# NSKPD.net
KiCad netlist of a schematic drawn in Altium Designer
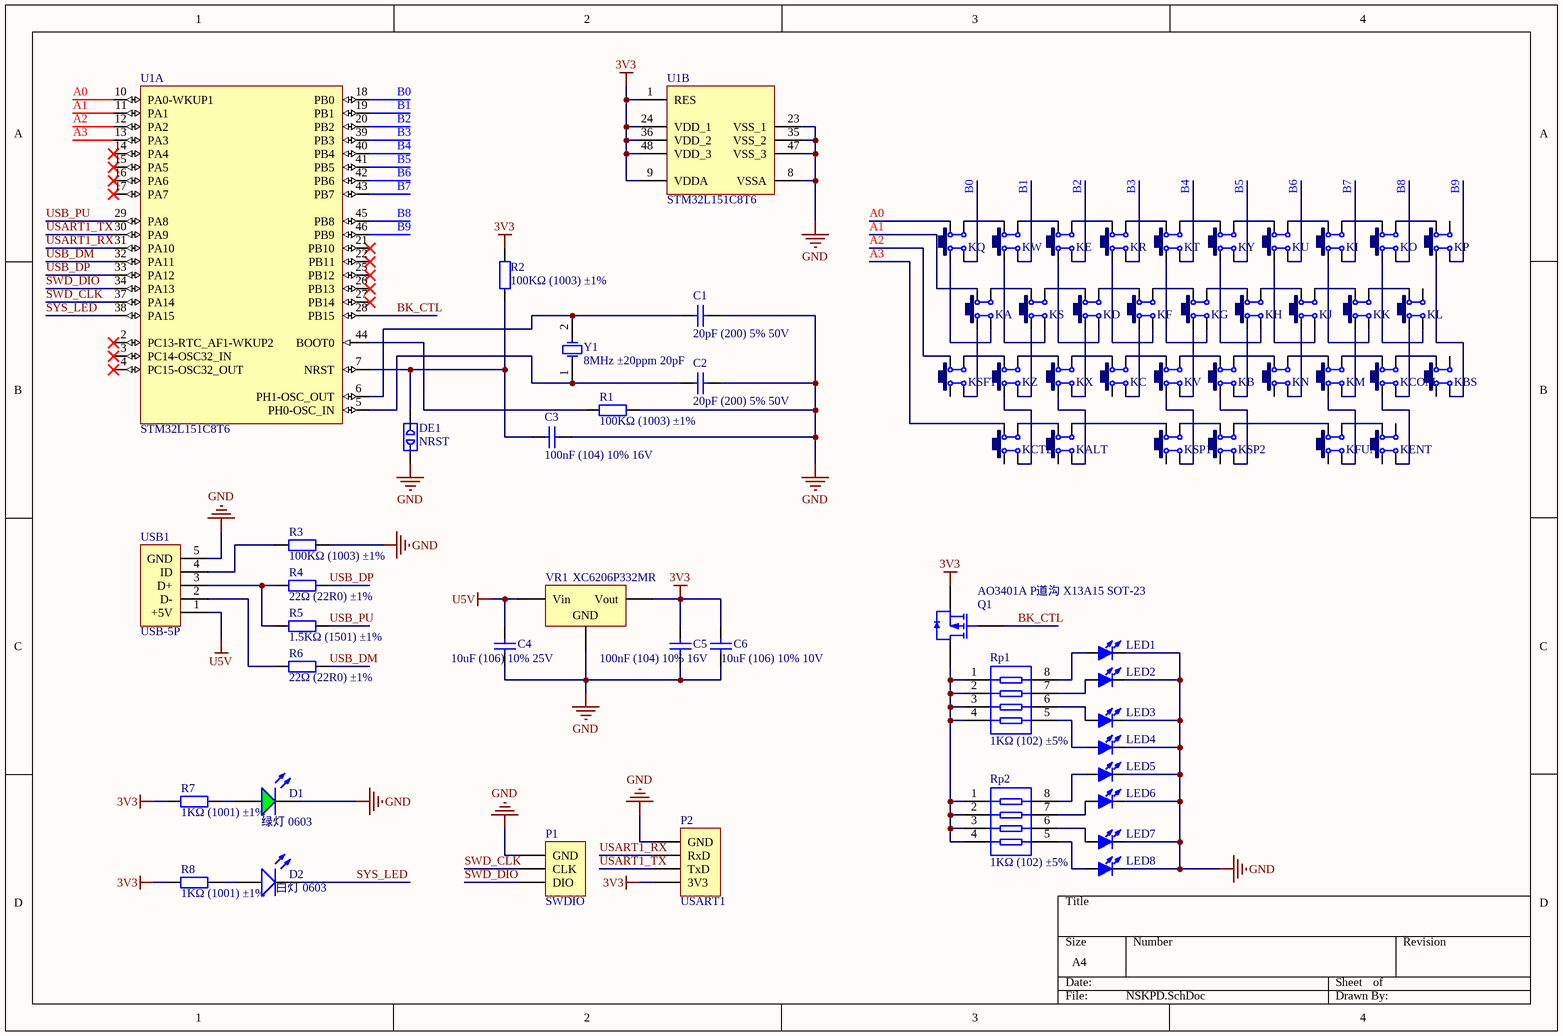
[diagram p0: NSKPD.SchDoc]

(export (version "E")
  (design (tool "Eeschema 10.0.6"))
  (components
    (comp (ref "C1")
      (value "20pF (200) 5% 50V")
      (footprint "0402_C")
      (description "贴片电容")
      (libsource (lib "Miscellaneous Devices LC") (part "0402 20pF (200) 5% 50V"))
    )
    (comp (ref "C2")
      (value "20pF (200) 5% 50V")
      (footprint "0402_C")
      (description "贴片电容")
      (libsource (lib "Miscellaneous Devices LC") (part "0402 20pF (200) 5% 50V"))
    )
    (comp (ref "C3")
      (value "100nF (104) 10% 16V")
      (footprint "0402_C")
      (description "贴片电容")
      (libsource (lib "Miscellaneous Devices LC") (part "0402 100nF (104) 10% 16V"))
    )
    (comp (ref "C4")
      (value "10uF (106) 10% 25V")
      (footprint "0805_C")
      (description "贴片电容")
      (libsource (lib "Miscellaneous Devices LC") (part "0805 10uF (106) 10% 25V"))
    )
    (comp (ref "C5")
      (value "100nF (104) 10% 16V")
      (footprint "0402_C")
      (description "贴片电容")
      (libsource (lib "Miscellaneous Devices LC") (part "0402 100nF (104) 10% 16V"))
    )
    (comp (ref "C6")
      (value "10uF (106) 10% 10V")
      (footprint "0603_C")
      (description "贴片电容")
      (libsource (lib "Miscellaneous Devices LC") (part "0603 10uF (106) 10% 10V"))
    )
    (comp (ref "D1")
      (value "绿灯 0603")
      (footprint "0603_LED_S1")
      (description "发光二极管")
      (libsource (lib "Miscellaneous Devices LC") (part "0603 绿灯"))
    )
    (comp (ref "D2")
      (value "白灯 0603")
      (footprint "0603_LED_S1")
      (description "发光二极管")
      (libsource (lib "Miscellaneous Devices LC") (part "0603 白灯"))
    )
    (comp (ref "DE1")
      (value "NRST")
      (footprint "DEBUG_A")
      (description "调试断点焊盘")
      (fields (field (name "版权归属") "源创客"))
      (libsource (lib "15.1 - 未分类器件") (part "DEBUG"))
    )
    (comp (ref "KA")
      (value "6x6x5")
      (footprint "6*6*4.3 Small")
      (description "贴片6x6轻触开关")
      (fields (field (name "版权归属") "源创客"))
      (libsource (lib "5.1   - 按键-开关") (part "TSW SMD-6x6"))
    )
    (comp (ref "KALT")
      (value "6x6x5")
      (footprint "6*6*4.3 Small")
      (description "贴片6x6轻触开关")
      (fields (field (name "版权归属") "源创客"))
      (libsource (lib "5.1   - 按键-开关") (part "TSW SMD-6x6"))
    )
    (comp (ref "KB")
      (value "6x6x5")
      (footprint "6*6*4.3 Small")
      (description "贴片6x6轻触开关")
      (fields (field (name "版权归属") "源创客"))
      (libsource (lib "5.1   - 按键-开关") (part "TSW SMD-6x6"))
    )
    (comp (ref "KBS")
      (value "6x6x5")
      (footprint "6*6*4.3 Small")
      (description "贴片6x6轻触开关")
      (fields (field (name "版权归属") "源创客"))
      (libsource (lib "5.1   - 按键-开关") (part "TSW SMD-6x6"))
    )
    (comp (ref "KC")
      (value "6x6x5")
      (footprint "6*6*4.3 Small")
      (description "贴片6x6轻触开关")
      (fields (field (name "版权归属") "源创客"))
      (libsource (lib "5.1   - 按键-开关") (part "TSW SMD-6x6"))
    )
    (comp (ref "KCOM")
      (value "6x6x5")
      (footprint "6*6*4.3 Small")
      (description "贴片6x6轻触开关")
      (fields (field (name "版权归属") "源创客"))
      (libsource (lib "5.1   - 按键-开关") (part "TSW SMD-6x6"))
    )
    (comp (ref "KCTL")
      (value "6x6x5")
      (footprint "6*6*4.3 Small")
      (description "贴片6x6轻触开关")
      (fields (field (name "版权归属") "源创客"))
      (libsource (lib "5.1   - 按键-开关") (part "TSW SMD-6x6"))
    )
    (comp (ref "KD")
      (value "6x6x5")
      (footprint "6*6*4.3 Small")
      (description "贴片6x6轻触开关")
      (fields (field (name "版权归属") "源创客"))
      (libsource (lib "5.1   - 按键-开关") (part "TSW SMD-6x6"))
    )
    (comp (ref "KE")
      (value "6x6x5")
      (footprint "6*6*4.3 Small")
      (description "贴片6x6轻触开关")
      (fields (field (name "版权归属") "源创客"))
      (libsource (lib "5.1   - 按键-开关") (part "TSW SMD-6x6"))
    )
    (comp (ref "KENT")
      (value "6x6x5")
      (footprint "6*6*4.3 Small")
      (description "贴片6x6轻触开关")
      (fields (field (name "版权归属") "源创客"))
      (libsource (lib "5.1   - 按键-开关") (part "TSW SMD-6x6"))
    )
    (comp (ref "KF")
      (value "6x6x5")
      (footprint "6*6*4.3 Small")
      (description "贴片6x6轻触开关")
      (fields (field (name "版权归属") "源创客"))
      (libsource (lib "5.1   - 按键-开关") (part "TSW SMD-6x6"))
    )
    (comp (ref "KFUN")
      (value "6x6x5")
      (footprint "6*6*4.3 Small")
      (description "贴片6x6轻触开关")
      (fields (field (name "版权归属") "源创客"))
      (libsource (lib "5.1   - 按键-开关") (part "TSW SMD-6x6"))
    )
    (comp (ref "KG")
      (value "6x6x5")
      (footprint "6*6*4.3 Small")
      (description "贴片6x6轻触开关")
      (fields (field (name "版权归属") "源创客"))
      (libsource (lib "5.1   - 按键-开关") (part "TSW SMD-6x6"))
    )
    (comp (ref "KH")
      (value "6x6x5")
      (footprint "6*6*4.3 Small")
      (description "贴片6x6轻触开关")
      (fields (field (name "版权归属") "源创客"))
      (libsource (lib "5.1   - 按键-开关") (part "TSW SMD-6x6"))
    )
    (comp (ref "KI")
      (value "6x6x5")
      (footprint "6*6*4.3 Small")
      (description "贴片6x6轻触开关")
      (fields (field (name "版权归属") "源创客"))
      (libsource (lib "5.1   - 按键-开关") (part "TSW SMD-6x6"))
    )
    (comp (ref "KJ")
      (value "6x6x5")
      (footprint "6*6*4.3 Small")
      (description "贴片6x6轻触开关")
      (fields (field (name "版权归属") "源创客"))
      (libsource (lib "5.1   - 按键-开关") (part "TSW SMD-6x6"))
    )
    (comp (ref "KK")
      (value "6x6x5")
      (footprint "6*6*4.3 Small")
      (description "贴片6x6轻触开关")
      (fields (field (name "版权归属") "源创客"))
      (libsource (lib "5.1   - 按键-开关") (part "TSW SMD-6x6"))
    )
    (comp (ref "KL")
      (value "6x6x5")
      (footprint "6*6*4.3 Small")
      (description "贴片6x6轻触开关")
      (fields (field (name "版权归属") "源创客"))
      (libsource (lib "5.1   - 按键-开关") (part "TSW SMD-6x6"))
    )
    (comp (ref "KM")
      (value "6x6x5")
      (footprint "6*6*4.3 Small")
      (description "贴片6x6轻触开关")
      (fields (field (name "版权归属") "源创客"))
      (libsource (lib "5.1   - 按键-开关") (part "TSW SMD-6x6"))
    )
    (comp (ref "KN")
      (value "6x6x5")
      (footprint "6*6*4.3 Small")
      (description "贴片6x6轻触开关")
      (fields (field (name "版权归属") "源创客"))
      (libsource (lib "5.1   - 按键-开关") (part "TSW SMD-6x6"))
    )
    (comp (ref "KO")
      (value "6x6x5")
      (footprint "6*6*4.3 Small")
      (description "贴片6x6轻触开关")
      (fields (field (name "版权归属") "源创客"))
      (libsource (lib "5.1   - 按键-开关") (part "TSW SMD-6x6"))
    )
    (comp (ref "KP")
      (value "6x6x5")
      (footprint "6*6*4.3 Small")
      (description "贴片6x6轻触开关")
      (fields (field (name "版权归属") "源创客"))
      (libsource (lib "5.1   - 按键-开关") (part "TSW SMD-6x6"))
    )
    (comp (ref "KQ")
      (value "6x6x5")
      (footprint "6*6*4.3 Small")
      (description "贴片6x6轻触开关")
      (fields (field (name "版权归属") "源创客"))
      (libsource (lib "5.1   - 按键-开关") (part "TSW SMD-6x6"))
    )
    (comp (ref "KR")
      (value "6x6x5")
      (footprint "6*6*4.3 Small")
      (description "贴片6x6轻触开关")
      (fields (field (name "版权归属") "源创客"))
      (libsource (lib "5.1   - 按键-开关") (part "TSW SMD-6x6"))
    )
    (comp (ref "KS")
      (value "6x6x5")
      (footprint "6*6*4.3 Small")
      (description "贴片6x6轻触开关")
      (fields (field (name "版权归属") "源创客"))
      (libsource (lib "5.1   - 按键-开关") (part "TSW SMD-6x6"))
    )
    (comp (ref "KSFT")
      (value "6x6x5")
      (footprint "6*6*4.3 Small")
      (description "贴片6x6轻触开关")
      (fields (field (name "版权归属") "源创客"))
      (libsource (lib "5.1   - 按键-开关") (part "TSW SMD-6x6"))
    )
    (comp (ref "KSP1")
      (value "6x6x5")
      (footprint "6*6*4.3 Small")
      (description "贴片6x6轻触开关")
      (fields (field (name "版权归属") "源创客"))
      (libsource (lib "5.1   - 按键-开关") (part "TSW SMD-6x6"))
    )
    (comp (ref "KSP2")
      (value "6x6x5")
      (footprint "6*6*4.3 Small")
      (description "贴片6x6轻触开关")
      (fields (field (name "版权归属") "源创客"))
      (libsource (lib "5.1   - 按键-开关") (part "TSW SMD-6x6"))
    )
    (comp (ref "KT")
      (value "6x6x5")
      (footprint "6*6*4.3 Small")
      (description "贴片6x6轻触开关")
      (fields (field (name "版权归属") "源创客"))
      (libsource (lib "5.1   - 按键-开关") (part "TSW SMD-6x6"))
    )
    (comp (ref "KU")
      (value "6x6x5")
      (footprint "6*6*4.3 Small")
      (description "贴片6x6轻触开关")
      (fields (field (name "版权归属") "源创客"))
      (libsource (lib "5.1   - 按键-开关") (part "TSW SMD-6x6"))
    )
    (comp (ref "KV")
      (value "6x6x5")
      (footprint "6*6*4.3 Small")
      (description "贴片6x6轻触开关")
      (fields (field (name "版权归属") "源创客"))
      (libsource (lib "5.1   - 按键-开关") (part "TSW SMD-6x6"))
    )
    (comp (ref "KW")
      (value "6x6x5")
      (footprint "6*6*4.3 Small")
      (description "贴片6x6轻触开关")
      (fields (field (name "版权归属") "源创客"))
      (libsource (lib "5.1   - 按键-开关") (part "TSW SMD-6x6"))
    )
    (comp (ref "KX")
      (value "6x6x5")
      (footprint "6*6*4.3 Small")
      (description "贴片6x6轻触开关")
      (fields (field (name "版权归属") "源创客"))
      (libsource (lib "5.1   - 按键-开关") (part "TSW SMD-6x6"))
    )
    (comp (ref "KY")
      (value "6x6x5")
      (footprint "6*6*4.3 Small")
      (description "贴片6x6轻触开关")
      (fields (field (name "版权归属") "源创客"))
      (libsource (lib "5.1   - 按键-开关") (part "TSW SMD-6x6"))
    )
    (comp (ref "KZ")
      (value "6x6x5")
      (footprint "6*6*4.3 Small")
      (description "贴片6x6轻触开关")
      (fields (field (name "版权归属") "源创客"))
      (libsource (lib "5.1   - 按键-开关") (part "TSW SMD-6x6"))
    )
    (comp (ref "LED1")
      (value "侧发光")
      (footprint "LED 0805W")
      (description "贴片LED")
      (fields (field (name "版权归属") "源创客"))
      (libsource (lib "9.1   - LED") (part "LED-SMD"))
    )
    (comp (ref "LED2")
      (value "侧发光")
      (footprint "LED 0805W")
      (description "贴片LED")
      (fields (field (name "版权归属") "源创客"))
      (libsource (lib "9.1   - LED") (part "LED-SMD"))
    )
    (comp (ref "LED3")
      (value "侧发光")
      (footprint "LED 0805W")
      (description "贴片LED")
      (fields (field (name "版权归属") "源创客"))
      (libsource (lib "9.1   - LED") (part "LED-SMD"))
    )
    (comp (ref "LED4")
      (value "侧发光")
      (footprint "LED 0805W")
      (description "贴片LED")
      (fields (field (name "版权归属") "源创客"))
      (libsource (lib "9.1   - LED") (part "LED-SMD"))
    )
    (comp (ref "LED5")
      (value "侧发光")
      (footprint "LED 0805W")
      (description "贴片LED")
      (fields (field (name "版权归属") "源创客"))
      (libsource (lib "9.1   - LED") (part "LED-SMD"))
    )
    (comp (ref "LED6")
      (value "侧发光")
      (footprint "LED 0805W")
      (description "贴片LED")
      (fields (field (name "版权归属") "源创客"))
      (libsource (lib "9.1   - LED") (part "LED-SMD"))
    )
    (comp (ref "LED7")
      (value "侧发光")
      (footprint "LED 0805W")
      (description "贴片LED")
      (fields (field (name "版权归属") "源创客"))
      (libsource (lib "9.1   - LED") (part "LED-SMD"))
    )
    (comp (ref "LED8")
      (value "侧发光")
      (footprint "LED 0805W")
      (description "贴片LED")
      (fields (field (name "版权归属") "源创客"))
      (libsource (lib "9.1   - LED") (part "LED-SMD"))
    )
    (comp (ref "P1")
      (value "SWDIO")
      (footprint "HDR1X3")
      (description "Header, 3-Pin")
      (fields (field (name "PUBLISHER") "Altium Limited"))
      (libsource (lib "Miscellaneous Connectors") (part "Header 3"))
    )
    (comp (ref "P2")
      (value "USART1")
      (footprint "HDR1X4")
      (description "Header, 4-Pin")
      (fields (field (name "PUBLISHER") "Altium Limited"))
      (libsource (lib "Miscellaneous Connectors") (part "Header 4"))
    )
    (comp (ref "Q1")
      (value "AO3401A P道沟 X13A15 SOT-23")
      (footprint "SOT-23-3L")
      (description "MOS(场效应管)")
      (libsource (lib "Miscellaneous Devices LC") (part "AO3401A P道沟 X13A15 SOT-23"))
    )
    (comp (ref "R1")
      (value "100KΩ (1003) ±1%")
      (footprint "0402_R")
      (description "贴片电阻")
      (libsource (lib "Miscellaneous Devices LC") (part "0402 100KΩ (1003) 1%"))
    )
    (comp (ref "R2")
      (value "100KΩ (1003) ±1%")
      (footprint "0402_R")
      (description "贴片电阻")
      (libsource (lib "") (part "0402 100KΩ (1003) 1%_1"))
    )
    (comp (ref "R3")
      (value "100KΩ (1003) ±1%")
      (footprint "0402_R")
      (description "贴片电阻")
      (libsource (lib "Miscellaneous Devices LC") (part "0402 100KΩ (1003) 1%"))
    )
    (comp (ref "R4")
      (value "22Ω (22R0) ±1%")
      (footprint "0402_R")
      (description "贴片电阻")
      (libsource (lib "Miscellaneous Devices LC") (part "0402 22Ω (22R0) 1%"))
    )
    (comp (ref "R5")
      (value "1.5KΩ (1501) ±1%")
      (footprint "0402_R")
      (description "贴片电阻")
      (libsource (lib "Miscellaneous Devices LC") (part "0402 1.5KΩ (1501) 1%"))
    )
    (comp (ref "R6")
      (value "22Ω (22R0) ±1%")
      (footprint "0402_R")
      (description "贴片电阻")
      (libsource (lib "Miscellaneous Devices LC") (part "0402 22Ω (22R0) 1%"))
    )
    (comp (ref "R7")
      (value "1KΩ (1001) ±1%")
      (footprint "0402_R")
      (description "贴片电阻")
      (libsource (lib "") (part "0402 1KΩ (1001) 1%_1"))
    )
    (comp (ref "R8")
      (value "1KΩ (1001) ±1%")
      (footprint "0402_R")
      (description "贴片电阻")
      (libsource (lib "Miscellaneous Devices LC") (part "0402 1KΩ (1001) 1%"))
    )
    (comp (ref "Rp1")
      (value "1KΩ (102) ±5%")
      (footprint "0402_Rx4")
      (description "贴片排阻")
      (libsource (lib "Miscellaneous Devices LC") (part "0402*4 1KΩ (102) 5%"))
    )
    (comp (ref "Rp2")
      (value "1KΩ (102) ±5%")
      (footprint "0402_Rx4")
      (description "贴片排阻")
      (libsource (lib "Miscellaneous Devices LC") (part "0402*4 1KΩ (102) 5%"))
    )
    (comp (ref "U1")
      (value "STM32L151C8T6")
      (footprint "LQFP-48_7x7x05P")
      (description "ARM")
      (libsource (lib "Miscellaneous Devices LC") (part "STM32L151C8T6"))
    )
    (comp (ref "USB1")
      (value "USB-5P")
      (footprint "USB-MICRO_D")
      (description "微型USB母座")
      (fields (field (name "版权归属") "源创客"))
      (libsource (lib "4.1   - 接口类") (part "USB-5P"))
    )
    (comp (ref "VR1")
      (value "XC6206P332MR")
      (footprint "SOT-23-3L")
      (description "低压差线性稳压(LDO)")
      (libsource (lib "Miscellaneous Devices LC") (part "SOT-23 XC6206P332MR"))
    )
    (comp (ref "Y1")
      (value "8MHz ±20ppm 20pF")
      (footprint "SMD-5032_2P")
      (description "贴片晶振")
      (libsource (lib "Miscellaneous Devices LC") (part "SMD-5032_2P 8MHz 20ppm 20pF"))
    )
  )
  (nets
    (net (code "1") (name "/A0") (class "Default")
      (node (ref "KQ") (pin "2") (pinfunction "2_2") (pintype "passive"))
      (node (ref "U1") (pin "10") (pinfunction "PA0-WKUP1_10") (pintype "bidirectional"))
    )
    (net (code "2") (name "/A1") (class "Default")
      (node (ref "KA") (pin "2") (pinfunction "2_2") (pintype "passive"))
      (node (ref "U1") (pin "11") (pinfunction "PA1_11") (pintype "bidirectional"))
    )
    (net (code "3") (name "/A2") (class "Default")
      (node (ref "KSFT") (pin "2") (pinfunction "2_2") (pintype "passive"))
      (node (ref "U1") (pin "12") (pinfunction "PA2_12") (pintype "bidirectional"))
    )
    (net (code "4") (name "/A3") (class "Default")
      (node (ref "KCTL") (pin "2") (pinfunction "2_2") (pintype "passive"))
      (node (ref "U1") (pin "13") (pinfunction "PA3_13") (pintype "bidirectional"))
    )
    (net (code "5") (name "/B0") (class "Default")
      (node (ref "KQ") (pin "4") (pinfunction "4_4") (pintype "passive"))
      (node (ref "U1") (pin "18") (pinfunction "PB0_18") (pintype "bidirectional"))
    )
    (net (code "6") (name "/B1") (class "Default")
      (node (ref "KW") (pin "4") (pinfunction "4_4") (pintype "passive"))
      (node (ref "U1") (pin "19") (pinfunction "PB1_19") (pintype "bidirectional"))
    )
    (net (code "7") (name "/B2") (class "Default")
      (node (ref "KE") (pin "4") (pinfunction "4_4") (pintype "passive"))
      (node (ref "U1") (pin "20") (pinfunction "PB2_20") (pintype "bidirectional"))
    )
    (net (code "8") (name "/B3") (class "Default")
      (node (ref "KR") (pin "4") (pinfunction "4_4") (pintype "passive"))
      (node (ref "U1") (pin "39") (pinfunction "PB3_39") (pintype "bidirectional"))
    )
    (net (code "9") (name "/B4") (class "Default")
      (node (ref "KT") (pin "4") (pinfunction "4_4") (pintype "passive"))
      (node (ref "U1") (pin "40") (pinfunction "PB4_40") (pintype "bidirectional"))
    )
    (net (code "10") (name "/B5") (class "Default")
      (node (ref "KY") (pin "4") (pinfunction "4_4") (pintype "passive"))
      (node (ref "U1") (pin "41") (pinfunction "PB5_41") (pintype "bidirectional"))
    )
    (net (code "11") (name "/B6") (class "Default")
      (node (ref "KU") (pin "4") (pinfunction "4_4") (pintype "passive"))
      (node (ref "U1") (pin "42") (pinfunction "PB6_42") (pintype "bidirectional"))
    )
    (net (code "12") (name "/B7") (class "Default")
      (node (ref "KI") (pin "4") (pinfunction "4_4") (pintype "passive"))
      (node (ref "U1") (pin "43") (pinfunction "PB7_43") (pintype "bidirectional"))
    )
    (net (code "13") (name "/B8") (class "Default")
      (node (ref "KO") (pin "4") (pinfunction "4_4") (pintype "passive"))
      (node (ref "U1") (pin "45") (pinfunction "PB8_45") (pintype "bidirectional"))
    )
    (net (code "14") (name "/B9") (class "Default")
      (node (ref "KP") (pin "4") (pinfunction "4_4") (pintype "passive"))
      (node (ref "U1") (pin "46") (pinfunction "PB9_46") (pintype "bidirectional"))
    )
    (net (code "15") (name "/BK_CTL") (class "Default")
      (node (ref "Q1") (pin "1") (pinfunction "G_1") (pintype "passive"))
      (node (ref "U1") (pin "28") (pinfunction "PB15_28") (pintype "bidirectional"))
    )
    (net (code "16") (name "/SWD_CLK") (class "Default")
      (node (ref "P1") (pin "2") (pinfunction "CLK_2") (pintype "passive"))
      (node (ref "U1") (pin "37") (pinfunction "PA14_37") (pintype "bidirectional"))
    )
    (net (code "17") (name "/SWD_DIO") (class "Default")
      (node (ref "P1") (pin "3") (pinfunction "DIO_3") (pintype "passive"))
      (node (ref "U1") (pin "34") (pinfunction "PA13_34") (pintype "bidirectional"))
    )
    (net (code "18") (name "/SYS_LED") (class "Default")
      (node (ref "D2") (pin "K") (pinfunction "K_K") (pintype "passive"))
      (node (ref "U1") (pin "38") (pinfunction "PA15_38") (pintype "bidirectional"))
    )
    (net (code "19") (name "/USART1_RX") (class "Default")
      (node (ref "P2") (pin "2") (pinfunction "RxD_2") (pintype "passive"))
      (node (ref "U1") (pin "31") (pinfunction "PA10_31") (pintype "bidirectional"))
    )
    (net (code "20") (name "/USART1_TX") (class "Default")
      (node (ref "P2") (pin "3") (pinfunction "TxD_3") (pintype "passive"))
      (node (ref "U1") (pin "30") (pinfunction "PA9_30") (pintype "bidirectional"))
    )
    (net (code "21") (name "/USB_DM") (class "Default")
      (node (ref "R6") (pin "2") (pinfunction "2_2") (pintype "passive"))
      (node (ref "U1") (pin "32") (pinfunction "PA11_32") (pintype "bidirectional"))
    )
    (net (code "22") (name "/USB_DP") (class "Default")
      (node (ref "R4") (pin "2") (pinfunction "2_2") (pintype "passive"))
      (node (ref "U1") (pin "33") (pinfunction "PA12_33") (pintype "bidirectional"))
    )
    (net (code "23") (name "/USB_PU") (class "Default")
      (node (ref "R5") (pin "2") (pinfunction "2_2") (pintype "passive"))
      (node (ref "U1") (pin "29") (pinfunction "PA8_29") (pintype "bidirectional"))
    )
    (net (code "24") (name "3V3") (class "Default")
      (node (ref "C5") (pin "2") (pinfunction "2_2") (pintype "passive"))
      (node (ref "C6") (pin "2") (pinfunction "2_2") (pintype "passive"))
      (node (ref "P2") (pin "4") (pinfunction "3V3_4") (pintype "passive"))
      (node (ref "Q1") (pin "2") (pinfunction "S_2") (pintype "passive"))
      (node (ref "R2") (pin "2") (pinfunction "2_2") (pintype "passive"))
      (node (ref "R7") (pin "1") (pinfunction "1_1") (pintype "passive"))
      (node (ref "R8") (pin "2") (pinfunction "2_2") (pintype "passive"))
      (node (ref "U1") (pin "1") (pinfunction "RES_1") (pintype "power_in"))
      (node (ref "U1") (pin "24") (pinfunction "VDD_1_24") (pintype "power_in"))
      (node (ref "U1") (pin "36") (pinfunction "VDD_2_36") (pintype "power_in"))
      (node (ref "U1") (pin "48") (pinfunction "VDD_3_48") (pintype "power_in"))
      (node (ref "U1") (pin "9") (pinfunction "VDDA_9") (pintype "power_in"))
      (node (ref "VR1") (pin "2") (pinfunction "Vout_2") (pintype "passive"))
    )
    (net (code "25") (name "GND") (class "Default")
      (node (ref "C1") (pin "2") (pinfunction "2_2") (pintype "passive"))
      (node (ref "C2") (pin "2") (pinfunction "2_2") (pintype "passive"))
      (node (ref "C3") (pin "1") (pinfunction "1_1") (pintype "passive"))
      (node (ref "C4") (pin "1") (pinfunction "1_1") (pintype "passive"))
      (node (ref "C5") (pin "1") (pinfunction "1_1") (pintype "passive"))
      (node (ref "C6") (pin "1") (pinfunction "1_1") (pintype "passive"))
      (node (ref "D1") (pin "K") (pinfunction "K_K") (pintype "passive"))
      (node (ref "DE1") (pin "2") (pinfunction "2_2") (pintype "passive"))
      (node (ref "LED1") (pin "2") (pinfunction "K_2") (pintype "passive"))
      (node (ref "LED2") (pin "2") (pinfunction "K_2") (pintype "passive"))
      (node (ref "LED3") (pin "2") (pinfunction "K_2") (pintype "passive"))
      (node (ref "LED4") (pin "2") (pinfunction "K_2") (pintype "passive"))
      (node (ref "LED5") (pin "2") (pinfunction "K_2") (pintype "passive"))
      (node (ref "LED6") (pin "2") (pinfunction "K_2") (pintype "passive"))
      (node (ref "LED7") (pin "2") (pinfunction "K_2") (pintype "passive"))
      (node (ref "LED8") (pin "2") (pinfunction "K_2") (pintype "passive"))
      (node (ref "P1") (pin "1") (pinfunction "GND_1") (pintype "passive"))
      (node (ref "P2") (pin "1") (pinfunction "GND_1") (pintype "passive"))
      (node (ref "R1") (pin "2") (pinfunction "2_2") (pintype "passive"))
      (node (ref "R3") (pin "2") (pinfunction "2_2") (pintype "passive"))
      (node (ref "U1") (pin "23") (pinfunction "VSS_1_23") (pintype "power_in"))
      (node (ref "U1") (pin "35") (pinfunction "VSS_2_35") (pintype "power_in"))
      (node (ref "U1") (pin "47") (pinfunction "VSS_3_47") (pintype "power_in"))
      (node (ref "U1") (pin "8") (pinfunction "VSSA_8") (pintype "power_in"))
      (node (ref "USB1") (pin "5") (pinfunction "GND_5") (pintype "passive"))
      (node (ref "VR1") (pin "1") (pinfunction "GND_1") (pintype "passive"))
    )
    (net (code "26") (name "Net-(D1-PadA)") (class "Default")
      (node (ref "D1") (pin "A") (pinfunction "A_A") (pintype "passive"))
      (node (ref "R7") (pin "2") (pinfunction "2_2") (pintype "passive"))
    )
    (net (code "27") (name "Net-(D2-PadA)") (class "Default")
      (node (ref "D2") (pin "A") (pinfunction "A_A") (pintype "passive"))
      (node (ref "R8") (pin "1") (pinfunction "1_1") (pintype "passive"))
    )
    (net (code "28") (name "Net-(KA-Pad1)") (class "Default")
      (node (ref "KA") (pin "1") (pinfunction "1_1") (pintype "passive"))
      (node (ref "KSFT") (pin "4") (pinfunction "4_4") (pintype "passive"))
    )
    (net (code "29") (name "Net-(KA-Pad3)") (class "Default")
      (node (ref "KA") (pin "3") (pinfunction "3_3") (pintype "passive"))
      (node (ref "KS") (pin "2") (pinfunction "2_2") (pintype "passive"))
    )
    (net (code "30") (name "Net-(KA-Pad4)") (class "Default")
      (node (ref "KA") (pin "4") (pinfunction "4_4") (pintype "passive"))
      (node (ref "KQ") (pin "1") (pinfunction "1_1") (pintype "passive"))
    )
    (net (code "31") (name "Net-(KALT-Pad2)") (class "Default")
      (node (ref "KALT") (pin "2") (pinfunction "2_2") (pintype "passive"))
      (node (ref "KCTL") (pin "3") (pinfunction "3_3") (pintype "passive"))
    )
    (net (code "32") (name "Net-(KALT-Pad3)") (class "Default")
      (node (ref "KALT") (pin "3") (pinfunction "3_3") (pintype "passive"))
      (node (ref "KSP1") (pin "2") (pinfunction "2_2") (pintype "passive"))
    )
    (net (code "33") (name "Net-(KALT-Pad4)") (class "Default")
      (node (ref "KALT") (pin "4") (pinfunction "4_4") (pintype "passive"))
      (node (ref "KX") (pin "1") (pinfunction "1_1") (pintype "passive"))
    )
    (net (code "34") (name "Net-(KB-Pad1)") (class "Default")
      (node (ref "KB") (pin "1") (pinfunction "1_1") (pintype "passive"))
      (node (ref "KSP2") (pin "4") (pinfunction "4_4") (pintype "passive"))
    )
    (net (code "35") (name "Net-(KB-Pad2)") (class "Default")
      (node (ref "KB") (pin "2") (pinfunction "2_2") (pintype "passive"))
      (node (ref "KV") (pin "3") (pinfunction "3_3") (pintype "passive"))
    )
    (net (code "36") (name "Net-(KB-Pad3)") (class "Default")
      (node (ref "KB") (pin "3") (pinfunction "3_3") (pintype "passive"))
      (node (ref "KN") (pin "2") (pinfunction "2_2") (pintype "passive"))
    )
    (net (code "37") (name "Net-(KB-Pad4)") (class "Default")
      (node (ref "KB") (pin "4") (pinfunction "4_4") (pintype "passive"))
      (node (ref "KH") (pin "1") (pinfunction "1_1") (pintype "passive"))
    )
    (net (code "38") (name "Net-(KBS-Pad2)") (class "Default")
      (node (ref "KBS") (pin "2") (pinfunction "2_2") (pintype "passive"))
      (node (ref "KCOM") (pin "3") (pinfunction "3_3") (pintype "passive"))
    )
    (net (code "39") (name "Net-(KBS-Pad4)") (class "Default")
      (node (ref "KBS") (pin "4") (pinfunction "4_4") (pintype "passive"))
      (node (ref "KP") (pin "1") (pinfunction "1_1") (pintype "passive"))
    )
    (net (code "40") (name "Net-(KC-Pad2)") (class "Default")
      (node (ref "KC") (pin "2") (pinfunction "2_2") (pintype "passive"))
      (node (ref "KX") (pin "3") (pinfunction "3_3") (pintype "passive"))
    )
    (net (code "41") (name "Net-(KC-Pad3)") (class "Default")
      (node (ref "KC") (pin "3") (pinfunction "3_3") (pintype "passive"))
      (node (ref "KV") (pin "2") (pinfunction "2_2") (pintype "passive"))
    )
    (net (code "42") (name "Net-(KC-Pad4)") (class "Default")
      (node (ref "KC") (pin "4") (pinfunction "4_4") (pintype "passive"))
      (node (ref "KF") (pin "1") (pinfunction "1_1") (pintype "passive"))
    )
    (net (code "43") (name "Net-(KCOM-Pad1)") (class "Default")
      (node (ref "KCOM") (pin "1") (pinfunction "1_1") (pintype "passive"))
      (node (ref "KENT") (pin "4") (pinfunction "4_4") (pintype "passive"))
    )
    (net (code "44") (name "Net-(KCOM-Pad2)") (class "Default")
      (node (ref "KCOM") (pin "2") (pinfunction "2_2") (pintype "passive"))
      (node (ref "KM") (pin "3") (pinfunction "3_3") (pintype "passive"))
    )
    (net (code "45") (name "Net-(KCOM-Pad4)") (class "Default")
      (node (ref "KCOM") (pin "4") (pinfunction "4_4") (pintype "passive"))
      (node (ref "KL") (pin "1") (pinfunction "1_1") (pintype "passive"))
    )
    (net (code "46") (name "Net-(KCTL-Pad4)") (class "Default")
      (node (ref "KCTL") (pin "4") (pinfunction "4_4") (pintype "passive"))
      (node (ref "KZ") (pin "1") (pinfunction "1_1") (pintype "passive"))
    )
    (net (code "47") (name "Net-(KD-Pad1)") (class "Default")
      (node (ref "KD") (pin "1") (pinfunction "1_1") (pintype "passive"))
      (node (ref "KX") (pin "4") (pinfunction "4_4") (pintype "passive"))
    )
    (net (code "48") (name "Net-(KD-Pad2)") (class "Default")
      (node (ref "KD") (pin "2") (pinfunction "2_2") (pintype "passive"))
      (node (ref "KS") (pin "3") (pinfunction "3_3") (pintype "passive"))
    )
    (net (code "49") (name "Net-(KD-Pad3)") (class "Default")
      (node (ref "KD") (pin "3") (pinfunction "3_3") (pintype "passive"))
      (node (ref "KF") (pin "2") (pinfunction "2_2") (pintype "passive"))
    )
    (net (code "50") (name "Net-(KD-Pad4)") (class "Default")
      (node (ref "KD") (pin "4") (pinfunction "4_4") (pintype "passive"))
      (node (ref "KE") (pin "1") (pinfunction "1_1") (pintype "passive"))
    )
    (net (code "51") (name "Net-(KE-Pad2)") (class "Default")
      (node (ref "KE") (pin "2") (pinfunction "2_2") (pintype "passive"))
      (node (ref "KW") (pin "3") (pinfunction "3_3") (pintype "passive"))
    )
    (net (code "52") (name "Net-(KE-Pad3)") (class "Default")
      (node (ref "KE") (pin "3") (pinfunction "3_3") (pintype "passive"))
      (node (ref "KR") (pin "2") (pinfunction "2_2") (pintype "passive"))
    )
    (net (code "53") (name "Net-(KENT-Pad2)") (class "Default")
      (node (ref "KENT") (pin "2") (pinfunction "2_2") (pintype "passive"))
      (node (ref "KFUN") (pin "3") (pinfunction "3_3") (pintype "passive"))
    )
    (net (code "54") (name "Net-(KF-Pad3)") (class "Default")
      (node (ref "KF") (pin "3") (pinfunction "3_3") (pintype "passive"))
      (node (ref "KG") (pin "2") (pinfunction "2_2") (pintype "passive"))
    )
    (net (code "55") (name "Net-(KF-Pad4)") (class "Default")
      (node (ref "KF") (pin "4") (pinfunction "4_4") (pintype "passive"))
      (node (ref "KR") (pin "1") (pinfunction "1_1") (pintype "passive"))
    )
    (net (code "56") (name "Net-(KFUN-Pad2)") (class "Default")
      (node (ref "KFUN") (pin "2") (pinfunction "2_2") (pintype "passive"))
      (node (ref "KSP2") (pin "3") (pinfunction "3_3") (pintype "passive"))
    )
    (net (code "57") (name "Net-(KFUN-Pad4)") (class "Default")
      (node (ref "KFUN") (pin "4") (pinfunction "4_4") (pintype "passive"))
      (node (ref "KM") (pin "1") (pinfunction "1_1") (pintype "passive"))
    )
    (net (code "58") (name "Net-(KG-Pad1)") (class "Default")
      (node (ref "KG") (pin "1") (pinfunction "1_1") (pintype "passive"))
      (node (ref "KV") (pin "4") (pinfunction "4_4") (pintype "passive"))
    )
    (net (code "59") (name "Net-(KG-Pad3)") (class "Default")
      (node (ref "KG") (pin "3") (pinfunction "3_3") (pintype "passive"))
      (node (ref "KH") (pin "2") (pinfunction "2_2") (pintype "passive"))
    )
    (net (code "60") (name "Net-(KG-Pad4)") (class "Default")
      (node (ref "KG") (pin "4") (pinfunction "4_4") (pintype "passive"))
      (node (ref "KT") (pin "1") (pinfunction "1_1") (pintype "passive"))
    )
    (net (code "61") (name "Net-(KH-Pad3)") (class "Default")
      (node (ref "KH") (pin "3") (pinfunction "3_3") (pintype "passive"))
      (node (ref "KJ") (pin "2") (pinfunction "2_2") (pintype "passive"))
    )
    (net (code "62") (name "Net-(KH-Pad4)") (class "Default")
      (node (ref "KH") (pin "4") (pinfunction "4_4") (pintype "passive"))
      (node (ref "KY") (pin "1") (pinfunction "1_1") (pintype "passive"))
    )
    (net (code "63") (name "Net-(KI-Pad1)") (class "Default")
      (node (ref "KI") (pin "1") (pinfunction "1_1") (pintype "passive"))
      (node (ref "KK") (pin "4") (pinfunction "4_4") (pintype "passive"))
    )
    (net (code "64") (name "Net-(KI-Pad2)") (class "Default")
      (node (ref "KI") (pin "2") (pinfunction "2_2") (pintype "passive"))
      (node (ref "KU") (pin "3") (pinfunction "3_3") (pintype "passive"))
    )
    (net (code "65") (name "Net-(KI-Pad3)") (class "Default")
      (node (ref "KI") (pin "3") (pinfunction "3_3") (pintype "passive"))
      (node (ref "KO") (pin "2") (pinfunction "2_2") (pintype "passive"))
    )
    (net (code "66") (name "Net-(KJ-Pad1)") (class "Default")
      (node (ref "KJ") (pin "1") (pinfunction "1_1") (pintype "passive"))
      (node (ref "KN") (pin "4") (pinfunction "4_4") (pintype "passive"))
    )
    (net (code "67") (name "Net-(KJ-Pad3)") (class "Default")
      (node (ref "KJ") (pin "3") (pinfunction "3_3") (pintype "passive"))
      (node (ref "KK") (pin "2") (pinfunction "2_2") (pintype "passive"))
    )
    (net (code "68") (name "Net-(KJ-Pad4)") (class "Default")
      (node (ref "KJ") (pin "4") (pinfunction "4_4") (pintype "passive"))
      (node (ref "KU") (pin "1") (pinfunction "1_1") (pintype "passive"))
    )
    (net (code "69") (name "Net-(KK-Pad1)") (class "Default")
      (node (ref "KK") (pin "1") (pinfunction "1_1") (pintype "passive"))
      (node (ref "KM") (pin "4") (pinfunction "4_4") (pintype "passive"))
    )
    (net (code "70") (name "Net-(KK-Pad3)") (class "Default")
      (node (ref "KK") (pin "3") (pinfunction "3_3") (pintype "passive"))
      (node (ref "KL") (pin "2") (pinfunction "2_2") (pintype "passive"))
    )
    (net (code "71") (name "Net-(KL-Pad4)") (class "Default")
      (node (ref "KL") (pin "4") (pinfunction "4_4") (pintype "passive"))
      (node (ref "KO") (pin "1") (pinfunction "1_1") (pintype "passive"))
    )
    (net (code "72") (name "Net-(KM-Pad2)") (class "Default")
      (node (ref "KM") (pin "2") (pinfunction "2_2") (pintype "passive"))
      (node (ref "KN") (pin "3") (pinfunction "3_3") (pintype "passive"))
    )
    (net (code "73") (name "Net-(KO-Pad3)") (class "Default")
      (node (ref "KO") (pin "3") (pinfunction "3_3") (pintype "passive"))
      (node (ref "KP") (pin "2") (pinfunction "2_2") (pintype "passive"))
    )
    (net (code "74") (name "Net-(KQ-Pad3)") (class "Default")
      (node (ref "KQ") (pin "3") (pinfunction "3_3") (pintype "passive"))
      (node (ref "KW") (pin "2") (pinfunction "2_2") (pintype "passive"))
    )
    (net (code "75") (name "Net-(KR-Pad3)") (class "Default")
      (node (ref "KR") (pin "3") (pinfunction "3_3") (pintype "passive"))
      (node (ref "KT") (pin "2") (pinfunction "2_2") (pintype "passive"))
    )
    (net (code "76") (name "Net-(KS-Pad1)") (class "Default")
      (node (ref "KS") (pin "1") (pinfunction "1_1") (pintype "passive"))
      (node (ref "KZ") (pin "4") (pinfunction "4_4") (pintype "passive"))
    )
    (net (code "77") (name "Net-(KS-Pad4)") (class "Default")
      (node (ref "KS") (pin "4") (pinfunction "4_4") (pintype "passive"))
      (node (ref "KW") (pin "1") (pinfunction "1_1") (pintype "passive"))
    )
    (net (code "78") (name "Net-(KSFT-Pad3)") (class "Default")
      (node (ref "KSFT") (pin "3") (pinfunction "3_3") (pintype "passive"))
      (node (ref "KZ") (pin "2") (pinfunction "2_2") (pintype "passive"))
    )
    (net (code "79") (name "Net-(KSP1-Pad3)") (class "Default")
      (node (ref "KSP1") (pin "3") (pinfunction "3_3") (pintype "passive"))
      (node (ref "KSP2") (pin "2") (pinfunction "2_2") (pintype "passive"))
    )
    (net (code "80") (name "Net-(KSP1-Pad4)") (class "Default")
      (node (ref "KSP1") (pin "4") (pinfunction "4_4") (pintype "passive"))
      (node (ref "KV") (pin "1") (pinfunction "1_1") (pintype "passive"))
    )
    (net (code "81") (name "Net-(KT-Pad3)") (class "Default")
      (node (ref "KT") (pin "3") (pinfunction "3_3") (pintype "passive"))
      (node (ref "KY") (pin "2") (pinfunction "2_2") (pintype "passive"))
    )
    (net (code "82") (name "Net-(KU-Pad2)") (class "Default")
      (node (ref "KU") (pin "2") (pinfunction "2_2") (pintype "passive"))
      (node (ref "KY") (pin "3") (pinfunction "3_3") (pintype "passive"))
    )
    (net (code "83") (name "Net-(KX-Pad2)") (class "Default")
      (node (ref "KX") (pin "2") (pinfunction "2_2") (pintype "passive"))
      (node (ref "KZ") (pin "3") (pinfunction "3_3") (pintype "passive"))
    )
    (net (code "84") (name "Net-(LED1-A)") (class "Default")
      (node (ref "LED1") (pin "1") (pinfunction "A_1") (pintype "passive"))
      (node (ref "Rp1") (pin "8") (pinfunction "8_8") (pintype "passive"))
    )
    (net (code "85") (name "Net-(LED2-A)") (class "Default")
      (node (ref "LED2") (pin "1") (pinfunction "A_1") (pintype "passive"))
      (node (ref "Rp1") (pin "7") (pinfunction "7_7") (pintype "passive"))
    )
    (net (code "86") (name "Net-(LED3-A)") (class "Default")
      (node (ref "LED3") (pin "1") (pinfunction "A_1") (pintype "passive"))
      (node (ref "Rp1") (pin "6") (pinfunction "6_6") (pintype "passive"))
    )
    (net (code "87") (name "Net-(LED4-A)") (class "Default")
      (node (ref "LED4") (pin "1") (pinfunction "A_1") (pintype "passive"))
      (node (ref "Rp1") (pin "5") (pinfunction "5_5") (pintype "passive"))
    )
    (net (code "88") (name "Net-(LED5-A)") (class "Default")
      (node (ref "LED5") (pin "1") (pinfunction "A_1") (pintype "passive"))
      (node (ref "Rp2") (pin "8") (pinfunction "8_8") (pintype "passive"))
    )
    (net (code "89") (name "Net-(LED6-A)") (class "Default")
      (node (ref "LED6") (pin "1") (pinfunction "A_1") (pintype "passive"))
      (node (ref "Rp2") (pin "7") (pinfunction "7_7") (pintype "passive"))
    )
    (net (code "90") (name "Net-(LED7-A)") (class "Default")
      (node (ref "LED7") (pin "1") (pinfunction "A_1") (pintype "passive"))
      (node (ref "Rp2") (pin "6") (pinfunction "6_6") (pintype "passive"))
    )
    (net (code "91") (name "Net-(LED8-A)") (class "Default")
      (node (ref "LED8") (pin "1") (pinfunction "A_1") (pintype "passive"))
      (node (ref "Rp2") (pin "5") (pinfunction "5_5") (pintype "passive"))
    )
    (net (code "92") (name "Net-(Q1-D)") (class "Default")
      (node (ref "Q1") (pin "3") (pinfunction "D_3") (pintype "passive"))
      (node (ref "Rp1") (pin "1") (pinfunction "1_1") (pintype "passive"))
      (node (ref "Rp1") (pin "2") (pinfunction "2_2") (pintype "passive"))
      (node (ref "Rp1") (pin "3") (pinfunction "3_3") (pintype "passive"))
      (node (ref "Rp1") (pin "4") (pinfunction "4_4") (pintype "passive"))
      (node (ref "Rp2") (pin "1") (pinfunction "1_1") (pintype "passive"))
      (node (ref "Rp2") (pin "2") (pinfunction "2_2") (pintype "passive"))
      (node (ref "Rp2") (pin "3") (pinfunction "3_3") (pintype "passive"))
      (node (ref "Rp2") (pin "4") (pinfunction "4_4") (pintype "passive"))
    )
    (net (code "93") (name "Net-(U1A-BOOT0)") (class "Default")
      (node (ref "R1") (pin "1") (pinfunction "1_1") (pintype "passive"))
      (node (ref "U1") (pin "44") (pinfunction "BOOT0_44") (pintype "input"))
    )
    (net (code "94") (name "Net-(U1A-NRST)") (class "Default")
      (node (ref "C3") (pin "2") (pinfunction "2_2") (pintype "passive"))
      (node (ref "DE1") (pin "1") (pinfunction "1_1") (pintype "passive"))
      (node (ref "R2") (pin "1") (pinfunction "1_1") (pintype "passive"))
      (node (ref "U1") (pin "7") (pinfunction "NRST_7") (pintype "bidirectional"))
    )
    (net (code "95") (name "Net-(U1A-PH0-OSC_IN)") (class "Default")
      (node (ref "C2") (pin "1") (pinfunction "1_1") (pintype "passive"))
      (node (ref "U1") (pin "5") (pinfunction "PH0-OSC_IN_5") (pintype "bidirectional"))
      (node (ref "Y1") (pin "1") (pinfunction "OSC1_1") (pintype "passive"))
    )
    (net (code "96") (name "Net-(U1A-PH1-OSC_OUT)") (class "Default")
      (node (ref "C1") (pin "1") (pinfunction "1_1") (pintype "passive"))
      (node (ref "U1") (pin "6") (pinfunction "PH1-OSC_OUT_6") (pintype "bidirectional"))
      (node (ref "Y1") (pin "2") (pinfunction "OSC2_2") (pintype "passive"))
    )
    (net (code "97") (name "Net-(USB1-D+)") (class "Default")
      (node (ref "R4") (pin "1") (pinfunction "1_1") (pintype "passive"))
      (node (ref "R5") (pin "1") (pinfunction "1_1") (pintype "passive"))
      (node (ref "USB1") (pin "3") (pinfunction "D+_3") (pintype "passive"))
    )
    (net (code "98") (name "Net-(USB1-D-)") (class "Default")
      (node (ref "R6") (pin "1") (pinfunction "1_1") (pintype "passive"))
      (node (ref "USB1") (pin "2") (pinfunction "D-_2") (pintype "passive"))
    )
    (net (code "99") (name "Net-(USB1-ID)") (class "Default")
      (node (ref "R3") (pin "1") (pinfunction "1_1") (pintype "passive"))
      (node (ref "USB1") (pin "4") (pinfunction "ID_4") (pintype "passive"))
    )
    (net (code "100") (name "U5V") (class "Default")
      (node (ref "C4") (pin "2") (pinfunction "2_2") (pintype "passive"))
      (node (ref "USB1") (pin "1") (pinfunction "+5V_1") (pintype "passive"))
      (node (ref "VR1") (pin "3") (pinfunction "Vin_3") (pintype "passive"))
    )
    (net (code "101") (name "unconnected-(KALT-Pad1)") (class "Default")
      (node (ref "KALT") (pin "1") (pinfunction "1_1") (pintype "passive"))
    )
    (net (code "102") (name "unconnected-(KBS-Pad1)") (class "Default")
      (node (ref "KBS") (pin "1") (pinfunction "1_1") (pintype "passive"))
    )
    (net (code "103") (name "unconnected-(KBS-Pad3)") (class "Default")
      (node (ref "KBS") (pin "3") (pinfunction "3_3") (pintype "passive"))
    )
    (net (code "104") (name "unconnected-(KC-Pad1)") (class "Default")
      (node (ref "KC") (pin "1") (pinfunction "1_1") (pintype "passive"))
    )
    (net (code "105") (name "unconnected-(KCTL-Pad1)") (class "Default")
      (node (ref "KCTL") (pin "1") (pinfunction "1_1") (pintype "passive"))
    )
    (net (code "106") (name "unconnected-(KENT-Pad1)") (class "Default")
      (node (ref "KENT") (pin "1") (pinfunction "1_1") (pintype "passive"))
    )
    (net (code "107") (name "unconnected-(KENT-Pad3)") (class "Default")
      (node (ref "KENT") (pin "3") (pinfunction "3_3") (pintype "passive"))
    )
    (net (code "108") (name "unconnected-(KFUN-Pad1)") (class "Default")
      (node (ref "KFUN") (pin "1") (pinfunction "1_1") (pintype "passive"))
    )
    (net (code "109") (name "unconnected-(KL-Pad3)") (class "Default")
      (node (ref "KL") (pin "3") (pinfunction "3_3") (pintype "passive"))
    )
    (net (code "110") (name "unconnected-(KN-Pad1)") (class "Default")
      (node (ref "KN") (pin "1") (pinfunction "1_1") (pintype "passive"))
    )
    (net (code "111") (name "unconnected-(KP-Pad3)") (class "Default")
      (node (ref "KP") (pin "3") (pinfunction "3_3") (pintype "passive"))
    )
    (net (code "112") (name "unconnected-(KSFT-Pad1)") (class "Default")
      (node (ref "KSFT") (pin "1") (pinfunction "1_1") (pintype "passive"))
    )
    (net (code "113") (name "unconnected-(KSP1-Pad1)") (class "Default")
      (node (ref "KSP1") (pin "1") (pinfunction "1_1") (pintype "passive"))
    )
    (net (code "114") (name "unconnected-(KSP2-Pad1)") (class "Default")
      (node (ref "KSP2") (pin "1") (pinfunction "1_1") (pintype "passive"))
    )
    (net (code "115") (name "unconnected-(U1A-PA4-Pad14)") (class "Default")
      (node (ref "U1") (pin "14") (pinfunction "PA4_14") (pintype "bidirectional+no_connect"))
    )
    (net (code "116") (name "unconnected-(U1A-PA5-Pad15)") (class "Default")
      (node (ref "U1") (pin "15") (pinfunction "PA5_15") (pintype "bidirectional+no_connect"))
    )
    (net (code "117") (name "unconnected-(U1A-PA6-Pad16)") (class "Default")
      (node (ref "U1") (pin "16") (pinfunction "PA6_16") (pintype "bidirectional+no_connect"))
    )
    (net (code "118") (name "unconnected-(U1A-PA7-Pad17)") (class "Default")
      (node (ref "U1") (pin "17") (pinfunction "PA7_17") (pintype "bidirectional+no_connect"))
    )
    (net (code "119") (name "unconnected-(U1A-PB10-Pad21)") (class "Default")
      (node (ref "U1") (pin "21") (pinfunction "PB10_21") (pintype "bidirectional+no_connect"))
    )
    (net (code "120") (name "unconnected-(U1A-PB11-Pad22)") (class "Default")
      (node (ref "U1") (pin "22") (pinfunction "PB11_22") (pintype "bidirectional+no_connect"))
    )
    (net (code "121") (name "unconnected-(U1A-PB12-Pad25)") (class "Default")
      (node (ref "U1") (pin "25") (pinfunction "PB12_25") (pintype "bidirectional+no_connect"))
    )
    (net (code "122") (name "unconnected-(U1A-PB13-Pad26)") (class "Default")
      (node (ref "U1") (pin "26") (pinfunction "PB13_26") (pintype "bidirectional+no_connect"))
    )
    (net (code "123") (name "unconnected-(U1A-PB14-Pad27)") (class "Default")
      (node (ref "U1") (pin "27") (pinfunction "PB14_27") (pintype "bidirectional+no_connect"))
    )
    (net (code "124") (name "unconnected-(U1A-PC13-RTC_AF1-WKUP2-Pad2)") (class "Default")
      (node (ref "U1") (pin "2") (pinfunction "PC13-RTC_AF1-WKUP2_2") (pintype "bidirectional+no_connect"))
    )
    (net (code "125") (name "unconnected-(U1A-PC14-OSC32_IN-Pad3)") (class "Default")
      (node (ref "U1") (pin "3") (pinfunction "PC14-OSC32_IN_3") (pintype "bidirectional+no_connect"))
    )
    (net (code "126") (name "unconnected-(U1A-PC15-OSC32_OUT-Pad4)") (class "Default")
      (node (ref "U1") (pin "4") (pinfunction "PC15-OSC32_OUT_4") (pintype "bidirectional+no_connect"))
    )
  )
)
